# din-rail-distributor.net
KiCad netlist of a schematic drawn in EAGLE
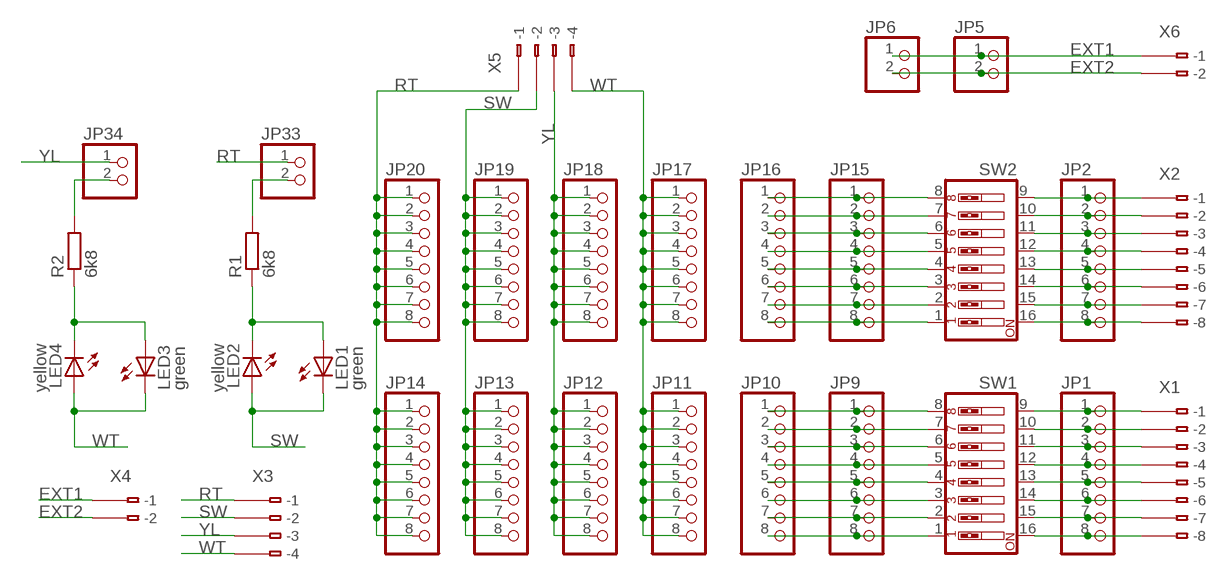
[diagram p0: schematic, sheet 1]

(export (version "E")
  (design (tool "Eeschema 10.0.6"))
  (components
    (comp (ref "JP1")
      (value "PINHD-1X8")
      (footprint "eagle-import:1X08")
      (libsource (lib "eagle-import") (part "PINHD-1X8"))
    )
    (comp (ref "JP2")
      (value "PINHD-1X8")
      (footprint "eagle-import:1X08")
      (libsource (lib "eagle-import") (part "PINHD-1X8"))
    )
    (comp (ref "JP5")
      (value "PINHD-1X2")
      (footprint "eagle-import:1X02")
      (libsource (lib "eagle-import") (part "PINHD-1X2"))
    )
    (comp (ref "JP6")
      (value "PINHD-1X2")
      (footprint "eagle-import:1X02")
      (libsource (lib "eagle-import") (part "PINHD-1X2"))
    )
    (comp (ref "JP9")
      (value "PINHD-1X8/SMALL")
      (footprint "eagle-import:1X08_SMALL")
      (libsource (lib "eagle-import") (part "PINHD-1X8/SMALL"))
    )
    (comp (ref "JP10")
      (value "PINHD-1X8/SMALL")
      (footprint "eagle-import:1X08_SMALL")
      (libsource (lib "eagle-import") (part "PINHD-1X8/SMALL"))
    )
    (comp (ref "JP11")
      (value "PINHD-1X8/SMALL")
      (footprint "eagle-import:1X08_SMALL")
      (libsource (lib "eagle-import") (part "PINHD-1X8/SMALL"))
    )
    (comp (ref "JP12")
      (value "PINHD-1X8/SMALL")
      (footprint "eagle-import:1X08_SMALL")
      (libsource (lib "eagle-import") (part "PINHD-1X8/SMALL"))
    )
    (comp (ref "JP13")
      (value "PINHD-1X8/SMALL")
      (footprint "eagle-import:1X08_SMALL")
      (libsource (lib "eagle-import") (part "PINHD-1X8/SMALL"))
    )
    (comp (ref "JP14")
      (value "PINHD-1X8/SMALL")
      (footprint "eagle-import:1X08_SMALL")
      (libsource (lib "eagle-import") (part "PINHD-1X8/SMALL"))
    )
    (comp (ref "JP15")
      (value "PINHD-1X8/SMALL")
      (footprint "eagle-import:1X08_SMALL")
      (libsource (lib "eagle-import") (part "PINHD-1X8/SMALL"))
    )
    (comp (ref "JP16")
      (value "PINHD-1X8/SMALL")
      (footprint "eagle-import:1X08_SMALL")
      (libsource (lib "eagle-import") (part "PINHD-1X8/SMALL"))
    )
    (comp (ref "JP17")
      (value "PINHD-1X8/SMALL")
      (footprint "eagle-import:1X08_SMALL")
      (libsource (lib "eagle-import") (part "PINHD-1X8/SMALL"))
    )
    (comp (ref "JP18")
      (value "PINHD-1X8/SMALL")
      (footprint "eagle-import:1X08_SMALL")
      (libsource (lib "eagle-import") (part "PINHD-1X8/SMALL"))
    )
    (comp (ref "JP19")
      (value "PINHD-1X8/SMALL")
      (footprint "eagle-import:1X08_SMALL")
      (libsource (lib "eagle-import") (part "PINHD-1X8/SMALL"))
    )
    (comp (ref "JP20")
      (value "PINHD-1X8/SMALL")
      (footprint "eagle-import:1X08_SMALL")
      (libsource (lib "eagle-import") (part "PINHD-1X8/SMALL"))
    )
    (comp (ref "JP33")
      (value "PINHD-1X2")
      (footprint "eagle-import:1X02")
      (libsource (lib "eagle-import") (part "PINHD-1X2"))
    )
    (comp (ref "JP34")
      (value "PINHD-1X2")
      (footprint "eagle-import:1X02")
      (libsource (lib "eagle-import") (part "PINHD-1X2"))
    )
    (comp (ref "LED1")
      (value "green")
      (footprint "eagle-import:CHIP-LED0603")
      (libsource (lib "eagle-import") (part "LEDCHIP-LED0603"))
    )
    (comp (ref "LED2")
      (value "yellow")
      (footprint "eagle-import:CHIP-LED0603")
      (libsource (lib "eagle-import") (part "LEDCHIP-LED0603"))
    )
    (comp (ref "LED3")
      (value "green")
      (footprint "eagle-import:CHIP-LED0603")
      (libsource (lib "eagle-import") (part "LEDCHIP-LED0603"))
    )
    (comp (ref "LED4")
      (value "yellow")
      (footprint "eagle-import:CHIP-LED0603")
      (libsource (lib "eagle-import") (part "LEDCHIP-LED0603"))
    )
    (comp (ref "R1")
      (value "6k8")
      (footprint "eagle-import:R1206")
      (libsource (lib "eagle-import") (part "R-EU_R1206"))
    )
    (comp (ref "R2")
      (value "6k8")
      (footprint "eagle-import:R1206")
      (libsource (lib "eagle-import") (part "R-EU_R1206"))
    )
    (comp (ref "SW1")
      (value "SW_DIP-8")
      (footprint "eagle-import:EDG-08")
      (libsource (lib "eagle-import") (part "SW_DIP-8"))
    )
    (comp (ref "SW2")
      (value "SW_DIP-8")
      (footprint "eagle-import:EDG-08")
      (libsource (lib "eagle-import") (part "SW_DIP-8"))
    )
    (comp (ref "X1")
      (value "233-108")
      (footprint "eagle-import:233-108")
      (libsource (lib "eagle-import") (part "233-108"))
    )
    (comp (ref "X2")
      (value "233-108")
      (footprint "eagle-import:233-108")
      (libsource (lib "eagle-import") (part "233-108"))
    )
    (comp (ref "X3")
      (value "233-104")
      (footprint "eagle-import:233-104")
      (libsource (lib "eagle-import") (part "233-104"))
    )
    (comp (ref "X4")
      (value "233-102")
      (footprint "eagle-import:233-102")
      (libsource (lib "eagle-import") (part "233-102"))
    )
    (comp (ref "X5")
      (value "233-104")
      (footprint "eagle-import:233-104")
      (libsource (lib "eagle-import") (part "233-104"))
    )
    (comp (ref "X6")
      (value "233-102")
      (footprint "eagle-import:233-102")
      (libsource (lib "eagle-import") (part "233-102"))
    )
  )
  (nets
    (net (code "1") (name "/EXT1") (class "Default")
      (node (ref "JP5") (pin "1") (pinfunction "1_1") (pintype "passive"))
      (node (ref "JP6") (pin "1") (pinfunction "1_1") (pintype "passive"))
      (node (ref "X4") (pin "B1") (pinfunction "B-1_B1") (pintype "passive"))
      (node (ref "X6") (pin "B1") (pinfunction "B-1_B1") (pintype "passive"))
    )
    (net (code "2") (name "/EXT2") (class "Default")
      (node (ref "JP5") (pin "2") (pinfunction "2_2") (pintype "passive"))
      (node (ref "JP6") (pin "2") (pinfunction "2_2") (pintype "passive"))
      (node (ref "X4") (pin "B2") (pinfunction "B-2_B2") (pintype "passive"))
      (node (ref "X6") (pin "B2") (pinfunction "B-2_B2") (pintype "passive"))
    )
    (net (code "3") (name "/RT") (class "Default")
      (node (ref "JP14") (pin "1") (pinfunction "1_1") (pintype "passive"))
      (node (ref "JP14") (pin "2") (pinfunction "2_2") (pintype "passive"))
      (node (ref "JP14") (pin "3") (pinfunction "3_3") (pintype "passive"))
      (node (ref "JP14") (pin "4") (pinfunction "4_4") (pintype "passive"))
      (node (ref "JP14") (pin "5") (pinfunction "5_5") (pintype "passive"))
      (node (ref "JP14") (pin "6") (pinfunction "6_6") (pintype "passive"))
      (node (ref "JP14") (pin "7") (pinfunction "7_7") (pintype "passive"))
      (node (ref "JP14") (pin "8") (pinfunction "8_8") (pintype "passive"))
      (node (ref "JP20") (pin "1") (pinfunction "1_1") (pintype "passive"))
      (node (ref "JP20") (pin "2") (pinfunction "2_2") (pintype "passive"))
      (node (ref "JP20") (pin "3") (pinfunction "3_3") (pintype "passive"))
      (node (ref "JP20") (pin "4") (pinfunction "4_4") (pintype "passive"))
      (node (ref "JP20") (pin "5") (pinfunction "5_5") (pintype "passive"))
      (node (ref "JP20") (pin "6") (pinfunction "6_6") (pintype "passive"))
      (node (ref "JP20") (pin "7") (pinfunction "7_7") (pintype "passive"))
      (node (ref "JP20") (pin "8") (pinfunction "8_8") (pintype "passive"))
      (node (ref "JP33") (pin "1") (pinfunction "1_1") (pintype "passive"))
      (node (ref "X3") (pin "B1") (pinfunction "B-1_B1") (pintype "passive"))
      (node (ref "X5") (pin "B1") (pinfunction "B-1_B1") (pintype "passive"))
    )
    (net (code "4") (name "/SW") (class "Default")
      (node (ref "JP13") (pin "1") (pinfunction "1_1") (pintype "passive"))
      (node (ref "JP13") (pin "2") (pinfunction "2_2") (pintype "passive"))
      (node (ref "JP13") (pin "3") (pinfunction "3_3") (pintype "passive"))
      (node (ref "JP13") (pin "4") (pinfunction "4_4") (pintype "passive"))
      (node (ref "JP13") (pin "5") (pinfunction "5_5") (pintype "passive"))
      (node (ref "JP13") (pin "6") (pinfunction "6_6") (pintype "passive"))
      (node (ref "JP13") (pin "7") (pinfunction "7_7") (pintype "passive"))
      (node (ref "JP13") (pin "8") (pinfunction "8_8") (pintype "passive"))
      (node (ref "JP19") (pin "1") (pinfunction "1_1") (pintype "passive"))
      (node (ref "JP19") (pin "2") (pinfunction "2_2") (pintype "passive"))
      (node (ref "JP19") (pin "3") (pinfunction "3_3") (pintype "passive"))
      (node (ref "JP19") (pin "4") (pinfunction "4_4") (pintype "passive"))
      (node (ref "JP19") (pin "5") (pinfunction "5_5") (pintype "passive"))
      (node (ref "JP19") (pin "6") (pinfunction "6_6") (pintype "passive"))
      (node (ref "JP19") (pin "7") (pinfunction "7_7") (pintype "passive"))
      (node (ref "JP19") (pin "8") (pinfunction "8_8") (pintype "passive"))
      (node (ref "LED1") (pin "C") (pinfunction "C_C") (pintype "passive"))
      (node (ref "LED2") (pin "A") (pinfunction "A_A") (pintype "passive"))
      (node (ref "X3") (pin "B2") (pinfunction "B-2_B2") (pintype "passive"))
      (node (ref "X5") (pin "B2") (pinfunction "B-2_B2") (pintype "passive"))
    )
    (net (code "5") (name "/WT") (class "Default")
      (node (ref "JP11") (pin "1") (pinfunction "1_1") (pintype "passive"))
      (node (ref "JP11") (pin "2") (pinfunction "2_2") (pintype "passive"))
      (node (ref "JP11") (pin "3") (pinfunction "3_3") (pintype "passive"))
      (node (ref "JP11") (pin "4") (pinfunction "4_4") (pintype "passive"))
      (node (ref "JP11") (pin "5") (pinfunction "5_5") (pintype "passive"))
      (node (ref "JP11") (pin "6") (pinfunction "6_6") (pintype "passive"))
      (node (ref "JP11") (pin "7") (pinfunction "7_7") (pintype "passive"))
      (node (ref "JP11") (pin "8") (pinfunction "8_8") (pintype "passive"))
      (node (ref "JP17") (pin "1") (pinfunction "1_1") (pintype "passive"))
      (node (ref "JP17") (pin "2") (pinfunction "2_2") (pintype "passive"))
      (node (ref "JP17") (pin "3") (pinfunction "3_3") (pintype "passive"))
      (node (ref "JP17") (pin "4") (pinfunction "4_4") (pintype "passive"))
      (node (ref "JP17") (pin "5") (pinfunction "5_5") (pintype "passive"))
      (node (ref "JP17") (pin "6") (pinfunction "6_6") (pintype "passive"))
      (node (ref "JP17") (pin "7") (pinfunction "7_7") (pintype "passive"))
      (node (ref "JP17") (pin "8") (pinfunction "8_8") (pintype "passive"))
      (node (ref "LED3") (pin "C") (pinfunction "C_C") (pintype "passive"))
      (node (ref "LED4") (pin "A") (pinfunction "A_A") (pintype "passive"))
      (node (ref "X3") (pin "B4") (pinfunction "B-4_B4") (pintype "passive"))
      (node (ref "X5") (pin "B4") (pinfunction "B-4_B4") (pintype "passive"))
    )
    (net (code "6") (name "/YL") (class "Default")
      (node (ref "JP12") (pin "1") (pinfunction "1_1") (pintype "passive"))
      (node (ref "JP12") (pin "2") (pinfunction "2_2") (pintype "passive"))
      (node (ref "JP12") (pin "3") (pinfunction "3_3") (pintype "passive"))
      (node (ref "JP12") (pin "4") (pinfunction "4_4") (pintype "passive"))
      (node (ref "JP12") (pin "5") (pinfunction "5_5") (pintype "passive"))
      (node (ref "JP12") (pin "6") (pinfunction "6_6") (pintype "passive"))
      (node (ref "JP12") (pin "7") (pinfunction "7_7") (pintype "passive"))
      (node (ref "JP12") (pin "8") (pinfunction "8_8") (pintype "passive"))
      (node (ref "JP18") (pin "1") (pinfunction "1_1") (pintype "passive"))
      (node (ref "JP18") (pin "2") (pinfunction "2_2") (pintype "passive"))
      (node (ref "JP18") (pin "3") (pinfunction "3_3") (pintype "passive"))
      (node (ref "JP18") (pin "4") (pinfunction "4_4") (pintype "passive"))
      (node (ref "JP18") (pin "5") (pinfunction "5_5") (pintype "passive"))
      (node (ref "JP18") (pin "6") (pinfunction "6_6") (pintype "passive"))
      (node (ref "JP18") (pin "7") (pinfunction "7_7") (pintype "passive"))
      (node (ref "JP18") (pin "8") (pinfunction "8_8") (pintype "passive"))
      (node (ref "JP34") (pin "1") (pinfunction "1_1") (pintype "passive"))
      (node (ref "X3") (pin "B3") (pinfunction "B-3_B3") (pintype "passive"))
      (node (ref "X5") (pin "B3") (pinfunction "B-3_B3") (pintype "passive"))
    )
    (net (code "7") (name "Net-(JP10-Pad1)") (class "Default")
      (node (ref "JP10") (pin "1") (pinfunction "1_1") (pintype "passive"))
      (node (ref "JP9") (pin "1") (pinfunction "1_1") (pintype "passive"))
      (node (ref "SW1") (pin "8") (pinfunction "8_8") (pintype "passive"))
    )
    (net (code "8") (name "Net-(JP10-Pad2)") (class "Default")
      (node (ref "JP10") (pin "2") (pinfunction "2_2") (pintype "passive"))
      (node (ref "JP9") (pin "2") (pinfunction "2_2") (pintype "passive"))
      (node (ref "SW1") (pin "7") (pinfunction "7_7") (pintype "passive"))
    )
    (net (code "9") (name "Net-(JP10-Pad3)") (class "Default")
      (node (ref "JP10") (pin "3") (pinfunction "3_3") (pintype "passive"))
      (node (ref "JP9") (pin "3") (pinfunction "3_3") (pintype "passive"))
      (node (ref "SW1") (pin "6") (pinfunction "6_6") (pintype "passive"))
    )
    (net (code "10") (name "Net-(JP10-Pad4)") (class "Default")
      (node (ref "JP10") (pin "4") (pinfunction "4_4") (pintype "passive"))
      (node (ref "JP9") (pin "4") (pinfunction "4_4") (pintype "passive"))
      (node (ref "SW1") (pin "5") (pinfunction "5_5") (pintype "passive"))
    )
    (net (code "11") (name "Net-(JP10-Pad5)") (class "Default")
      (node (ref "JP10") (pin "5") (pinfunction "5_5") (pintype "passive"))
      (node (ref "JP9") (pin "5") (pinfunction "5_5") (pintype "passive"))
      (node (ref "SW1") (pin "4") (pinfunction "4_4") (pintype "passive"))
    )
    (net (code "12") (name "Net-(JP10-Pad6)") (class "Default")
      (node (ref "JP10") (pin "6") (pinfunction "6_6") (pintype "passive"))
      (node (ref "JP9") (pin "6") (pinfunction "6_6") (pintype "passive"))
      (node (ref "SW1") (pin "3") (pinfunction "3_3") (pintype "passive"))
    )
    (net (code "13") (name "Net-(JP10-Pad7)") (class "Default")
      (node (ref "JP10") (pin "7") (pinfunction "7_7") (pintype "passive"))
      (node (ref "JP9") (pin "7") (pinfunction "7_7") (pintype "passive"))
      (node (ref "SW1") (pin "2") (pinfunction "2_2") (pintype "passive"))
    )
    (net (code "14") (name "Net-(JP10-Pad8)") (class "Default")
      (node (ref "JP10") (pin "8") (pinfunction "8_8") (pintype "passive"))
      (node (ref "JP9") (pin "8") (pinfunction "8_8") (pintype "passive"))
      (node (ref "SW1") (pin "1") (pinfunction "1_1") (pintype "passive"))
    )
    (net (code "15") (name "Net-(JP15-Pad1)") (class "Default")
      (node (ref "JP15") (pin "1") (pinfunction "1_1") (pintype "passive"))
      (node (ref "JP16") (pin "1") (pinfunction "1_1") (pintype "passive"))
      (node (ref "SW2") (pin "8") (pinfunction "8_8") (pintype "passive"))
    )
    (net (code "16") (name "Net-(JP15-Pad2)") (class "Default")
      (node (ref "JP15") (pin "2") (pinfunction "2_2") (pintype "passive"))
      (node (ref "JP16") (pin "2") (pinfunction "2_2") (pintype "passive"))
      (node (ref "SW2") (pin "7") (pinfunction "7_7") (pintype "passive"))
    )
    (net (code "17") (name "Net-(JP15-Pad3)") (class "Default")
      (node (ref "JP15") (pin "3") (pinfunction "3_3") (pintype "passive"))
      (node (ref "JP16") (pin "3") (pinfunction "3_3") (pintype "passive"))
      (node (ref "SW2") (pin "6") (pinfunction "6_6") (pintype "passive"))
    )
    (net (code "18") (name "Net-(JP15-Pad4)") (class "Default")
      (node (ref "JP15") (pin "4") (pinfunction "4_4") (pintype "passive"))
      (node (ref "JP16") (pin "4") (pinfunction "4_4") (pintype "passive"))
      (node (ref "SW2") (pin "5") (pinfunction "5_5") (pintype "passive"))
    )
    (net (code "19") (name "Net-(JP15-Pad5)") (class "Default")
      (node (ref "JP15") (pin "5") (pinfunction "5_5") (pintype "passive"))
      (node (ref "JP16") (pin "5") (pinfunction "5_5") (pintype "passive"))
      (node (ref "SW2") (pin "4") (pinfunction "4_4") (pintype "passive"))
    )
    (net (code "20") (name "Net-(JP15-Pad6)") (class "Default")
      (node (ref "JP15") (pin "6") (pinfunction "6_6") (pintype "passive"))
      (node (ref "JP16") (pin "6") (pinfunction "6_6") (pintype "passive"))
      (node (ref "SW2") (pin "3") (pinfunction "3_3") (pintype "passive"))
    )
    (net (code "21") (name "Net-(JP15-Pad7)") (class "Default")
      (node (ref "JP15") (pin "7") (pinfunction "7_7") (pintype "passive"))
      (node (ref "JP16") (pin "7") (pinfunction "7_7") (pintype "passive"))
      (node (ref "SW2") (pin "2") (pinfunction "2_2") (pintype "passive"))
    )
    (net (code "22") (name "Net-(JP15-Pad8)") (class "Default")
      (node (ref "JP15") (pin "8") (pinfunction "8_8") (pintype "passive"))
      (node (ref "JP16") (pin "8") (pinfunction "8_8") (pintype "passive"))
      (node (ref "SW2") (pin "1") (pinfunction "1_1") (pintype "passive"))
    )
    (net (code "23") (name "Net-(JP33-Pad2)") (class "Default")
      (node (ref "JP33") (pin "2") (pinfunction "2_2") (pintype "passive"))
      (node (ref "R1") (pin "2") (pinfunction "2_2") (pintype "passive"))
    )
    (net (code "24") (name "Net-(JP34-Pad2)") (class "Default")
      (node (ref "JP34") (pin "2") (pinfunction "2_2") (pintype "passive"))
      (node (ref "R2") (pin "2") (pinfunction "2_2") (pintype "passive"))
    )
    (net (code "25") (name "Net-(LED1-PadA)") (class "Default")
      (node (ref "LED1") (pin "A") (pinfunction "A_A") (pintype "passive"))
      (node (ref "LED2") (pin "C") (pinfunction "C_C") (pintype "passive"))
      (node (ref "R1") (pin "1") (pinfunction "1_1") (pintype "passive"))
    )
    (net (code "26") (name "Net-(LED3-PadA)") (class "Default")
      (node (ref "LED3") (pin "A") (pinfunction "A_A") (pintype "passive"))
      (node (ref "LED4") (pin "C") (pinfunction "C_C") (pintype "passive"))
      (node (ref "R2") (pin "1") (pinfunction "1_1") (pintype "passive"))
    )
    (net (code "27") (name "Net-(X1-B-1)") (class "Default")
      (node (ref "JP1") (pin "1") (pinfunction "1_1") (pintype "passive"))
      (node (ref "SW1") (pin "9") (pinfunction "9_9") (pintype "passive"))
      (node (ref "X1") (pin "B1") (pinfunction "B-1_B1") (pintype "passive"))
    )
    (net (code "28") (name "Net-(X1-B-2)") (class "Default")
      (node (ref "JP1") (pin "2") (pinfunction "2_2") (pintype "passive"))
      (node (ref "SW1") (pin "10") (pinfunction "10_10") (pintype "passive"))
      (node (ref "X1") (pin "B2") (pinfunction "B-2_B2") (pintype "passive"))
    )
    (net (code "29") (name "Net-(X1-B-3)") (class "Default")
      (node (ref "JP1") (pin "3") (pinfunction "3_3") (pintype "passive"))
      (node (ref "SW1") (pin "11") (pinfunction "11_11") (pintype "passive"))
      (node (ref "X1") (pin "B3") (pinfunction "B-3_B3") (pintype "passive"))
    )
    (net (code "30") (name "Net-(X1-B-4)") (class "Default")
      (node (ref "JP1") (pin "4") (pinfunction "4_4") (pintype "passive"))
      (node (ref "SW1") (pin "12") (pinfunction "12_12") (pintype "passive"))
      (node (ref "X1") (pin "B4") (pinfunction "B-4_B4") (pintype "passive"))
    )
    (net (code "31") (name "Net-(X1-B-5)") (class "Default")
      (node (ref "JP1") (pin "5") (pinfunction "5_5") (pintype "passive"))
      (node (ref "SW1") (pin "13") (pinfunction "13_13") (pintype "passive"))
      (node (ref "X1") (pin "B5") (pinfunction "B-5_B5") (pintype "passive"))
    )
    (net (code "32") (name "Net-(X1-B-6)") (class "Default")
      (node (ref "JP1") (pin "6") (pinfunction "6_6") (pintype "passive"))
      (node (ref "SW1") (pin "14") (pinfunction "14_14") (pintype "passive"))
      (node (ref "X1") (pin "B6") (pinfunction "B-6_B6") (pintype "passive"))
    )
    (net (code "33") (name "Net-(X1-B-7)") (class "Default")
      (node (ref "JP1") (pin "7") (pinfunction "7_7") (pintype "passive"))
      (node (ref "SW1") (pin "15") (pinfunction "15_15") (pintype "passive"))
      (node (ref "X1") (pin "B7") (pinfunction "B-7_B7") (pintype "passive"))
    )
    (net (code "34") (name "Net-(X1-B-8)") (class "Default")
      (node (ref "JP1") (pin "8") (pinfunction "8_8") (pintype "passive"))
      (node (ref "SW1") (pin "16") (pinfunction "16_16") (pintype "passive"))
      (node (ref "X1") (pin "B8") (pinfunction "B-8_B8") (pintype "passive"))
    )
    (net (code "35") (name "Net-(X2-B-1)") (class "Default")
      (node (ref "JP2") (pin "1") (pinfunction "1_1") (pintype "passive"))
      (node (ref "SW2") (pin "9") (pinfunction "9_9") (pintype "passive"))
      (node (ref "X2") (pin "B1") (pinfunction "B-1_B1") (pintype "passive"))
    )
    (net (code "36") (name "Net-(X2-B-2)") (class "Default")
      (node (ref "JP2") (pin "2") (pinfunction "2_2") (pintype "passive"))
      (node (ref "SW2") (pin "10") (pinfunction "10_10") (pintype "passive"))
      (node (ref "X2") (pin "B2") (pinfunction "B-2_B2") (pintype "passive"))
    )
    (net (code "37") (name "Net-(X2-B-3)") (class "Default")
      (node (ref "JP2") (pin "3") (pinfunction "3_3") (pintype "passive"))
      (node (ref "SW2") (pin "11") (pinfunction "11_11") (pintype "passive"))
      (node (ref "X2") (pin "B3") (pinfunction "B-3_B3") (pintype "passive"))
    )
    (net (code "38") (name "Net-(X2-B-4)") (class "Default")
      (node (ref "JP2") (pin "4") (pinfunction "4_4") (pintype "passive"))
      (node (ref "SW2") (pin "12") (pinfunction "12_12") (pintype "passive"))
      (node (ref "X2") (pin "B4") (pinfunction "B-4_B4") (pintype "passive"))
    )
    (net (code "39") (name "Net-(X2-B-5)") (class "Default")
      (node (ref "JP2") (pin "5") (pinfunction "5_5") (pintype "passive"))
      (node (ref "SW2") (pin "13") (pinfunction "13_13") (pintype "passive"))
      (node (ref "X2") (pin "B5") (pinfunction "B-5_B5") (pintype "passive"))
    )
    (net (code "40") (name "Net-(X2-B-6)") (class "Default")
      (node (ref "JP2") (pin "6") (pinfunction "6_6") (pintype "passive"))
      (node (ref "SW2") (pin "14") (pinfunction "14_14") (pintype "passive"))
      (node (ref "X2") (pin "B6") (pinfunction "B-6_B6") (pintype "passive"))
    )
    (net (code "41") (name "Net-(X2-B-7)") (class "Default")
      (node (ref "JP2") (pin "7") (pinfunction "7_7") (pintype "passive"))
      (node (ref "SW2") (pin "15") (pinfunction "15_15") (pintype "passive"))
      (node (ref "X2") (pin "B7") (pinfunction "B-7_B7") (pintype "passive"))
    )
    (net (code "42") (name "Net-(X2-B-8)") (class "Default")
      (node (ref "JP2") (pin "8") (pinfunction "8_8") (pintype "passive"))
      (node (ref "SW2") (pin "16") (pinfunction "16_16") (pintype "passive"))
      (node (ref "X2") (pin "B8") (pinfunction "B-8_B8") (pintype "passive"))
    )
    (net (code "43") (name "unconnected-(X1--1-PadA1)") (class "Default")
      (node (ref "X1") (pin "A1") (pinfunction "-1_A1") (pintype "passive"))
    )
    (net (code "44") (name "unconnected-(X1--2-PadA2)") (class "Default")
      (node (ref "X1") (pin "A2") (pinfunction "-2_A2") (pintype "passive"))
    )
    (net (code "45") (name "unconnected-(X1--3-PadA3)") (class "Default")
      (node (ref "X1") (pin "A3") (pinfunction "-3_A3") (pintype "passive"))
    )
    (net (code "46") (name "unconnected-(X1--4-PadA4)") (class "Default")
      (node (ref "X1") (pin "A4") (pinfunction "-4_A4") (pintype "passive"))
    )
    (net (code "47") (name "unconnected-(X1--5-PadA5)") (class "Default")
      (node (ref "X1") (pin "A5") (pinfunction "-5_A5") (pintype "passive"))
    )
    (net (code "48") (name "unconnected-(X1--6-PadA6)") (class "Default")
      (node (ref "X1") (pin "A6") (pinfunction "-6_A6") (pintype "passive"))
    )
    (net (code "49") (name "unconnected-(X1--7-PadA7)") (class "Default")
      (node (ref "X1") (pin "A7") (pinfunction "-7_A7") (pintype "passive"))
    )
    (net (code "50") (name "unconnected-(X1--8-PadA8)") (class "Default")
      (node (ref "X1") (pin "A8") (pinfunction "-8_A8") (pintype "passive"))
    )
    (net (code "51") (name "unconnected-(X2--1-PadA1)") (class "Default")
      (node (ref "X2") (pin "A1") (pinfunction "-1_A1") (pintype "passive"))
    )
    (net (code "52") (name "unconnected-(X2--2-PadA2)") (class "Default")
      (node (ref "X2") (pin "A2") (pinfunction "-2_A2") (pintype "passive"))
    )
    (net (code "53") (name "unconnected-(X2--3-PadA3)") (class "Default")
      (node (ref "X2") (pin "A3") (pinfunction "-3_A3") (pintype "passive"))
    )
    (net (code "54") (name "unconnected-(X2--4-PadA4)") (class "Default")
      (node (ref "X2") (pin "A4") (pinfunction "-4_A4") (pintype "passive"))
    )
    (net (code "55") (name "unconnected-(X2--5-PadA5)") (class "Default")
      (node (ref "X2") (pin "A5") (pinfunction "-5_A5") (pintype "passive"))
    )
    (net (code "56") (name "unconnected-(X2--6-PadA6)") (class "Default")
      (node (ref "X2") (pin "A6") (pinfunction "-6_A6") (pintype "passive"))
    )
    (net (code "57") (name "unconnected-(X2--7-PadA7)") (class "Default")
      (node (ref "X2") (pin "A7") (pinfunction "-7_A7") (pintype "passive"))
    )
    (net (code "58") (name "unconnected-(X2--8-PadA8)") (class "Default")
      (node (ref "X2") (pin "A8") (pinfunction "-8_A8") (pintype "passive"))
    )
    (net (code "59") (name "unconnected-(X3--1-PadA1)") (class "Default")
      (node (ref "X3") (pin "A1") (pinfunction "-1_A1") (pintype "passive"))
    )
    (net (code "60") (name "unconnected-(X3--2-PadA2)") (class "Default")
      (node (ref "X3") (pin "A2") (pinfunction "-2_A2") (pintype "passive"))
    )
    (net (code "61") (name "unconnected-(X3--3-PadA3)") (class "Default")
      (node (ref "X3") (pin "A3") (pinfunction "-3_A3") (pintype "passive"))
    )
    (net (code "62") (name "unconnected-(X3--4-PadA4)") (class "Default")
      (node (ref "X3") (pin "A4") (pinfunction "-4_A4") (pintype "passive"))
    )
    (net (code "63") (name "unconnected-(X4--1-PadA1)") (class "Default")
      (node (ref "X4") (pin "A1") (pinfunction "-1_A1") (pintype "passive"))
    )
    (net (code "64") (name "unconnected-(X4--2-PadA2)") (class "Default")
      (node (ref "X4") (pin "A2") (pinfunction "-2_A2") (pintype "passive"))
    )
    (net (code "65") (name "unconnected-(X5--1-PadA1)") (class "Default")
      (node (ref "X5") (pin "A1") (pinfunction "-1_A1") (pintype "passive"))
    )
    (net (code "66") (name "unconnected-(X5--2-PadA2)") (class "Default")
      (node (ref "X5") (pin "A2") (pinfunction "-2_A2") (pintype "passive"))
    )
    (net (code "67") (name "unconnected-(X5--3-PadA3)") (class "Default")
      (node (ref "X5") (pin "A3") (pinfunction "-3_A3") (pintype "passive"))
    )
    (net (code "68") (name "unconnected-(X5--4-PadA4)") (class "Default")
      (node (ref "X5") (pin "A4") (pinfunction "-4_A4") (pintype "passive"))
    )
    (net (code "69") (name "unconnected-(X6--1-PadA1)") (class "Default")
      (node (ref "X6") (pin "A1") (pinfunction "-1_A1") (pintype "passive"))
    )
    (net (code "70") (name "unconnected-(X6--2-PadA2)") (class "Default")
      (node (ref "X6") (pin "A2") (pinfunction "-2_A2") (pintype "passive"))
    )
  )
)
